# MUX_circuits.net
KiCad netlist of a schematic drawn in EAGLE
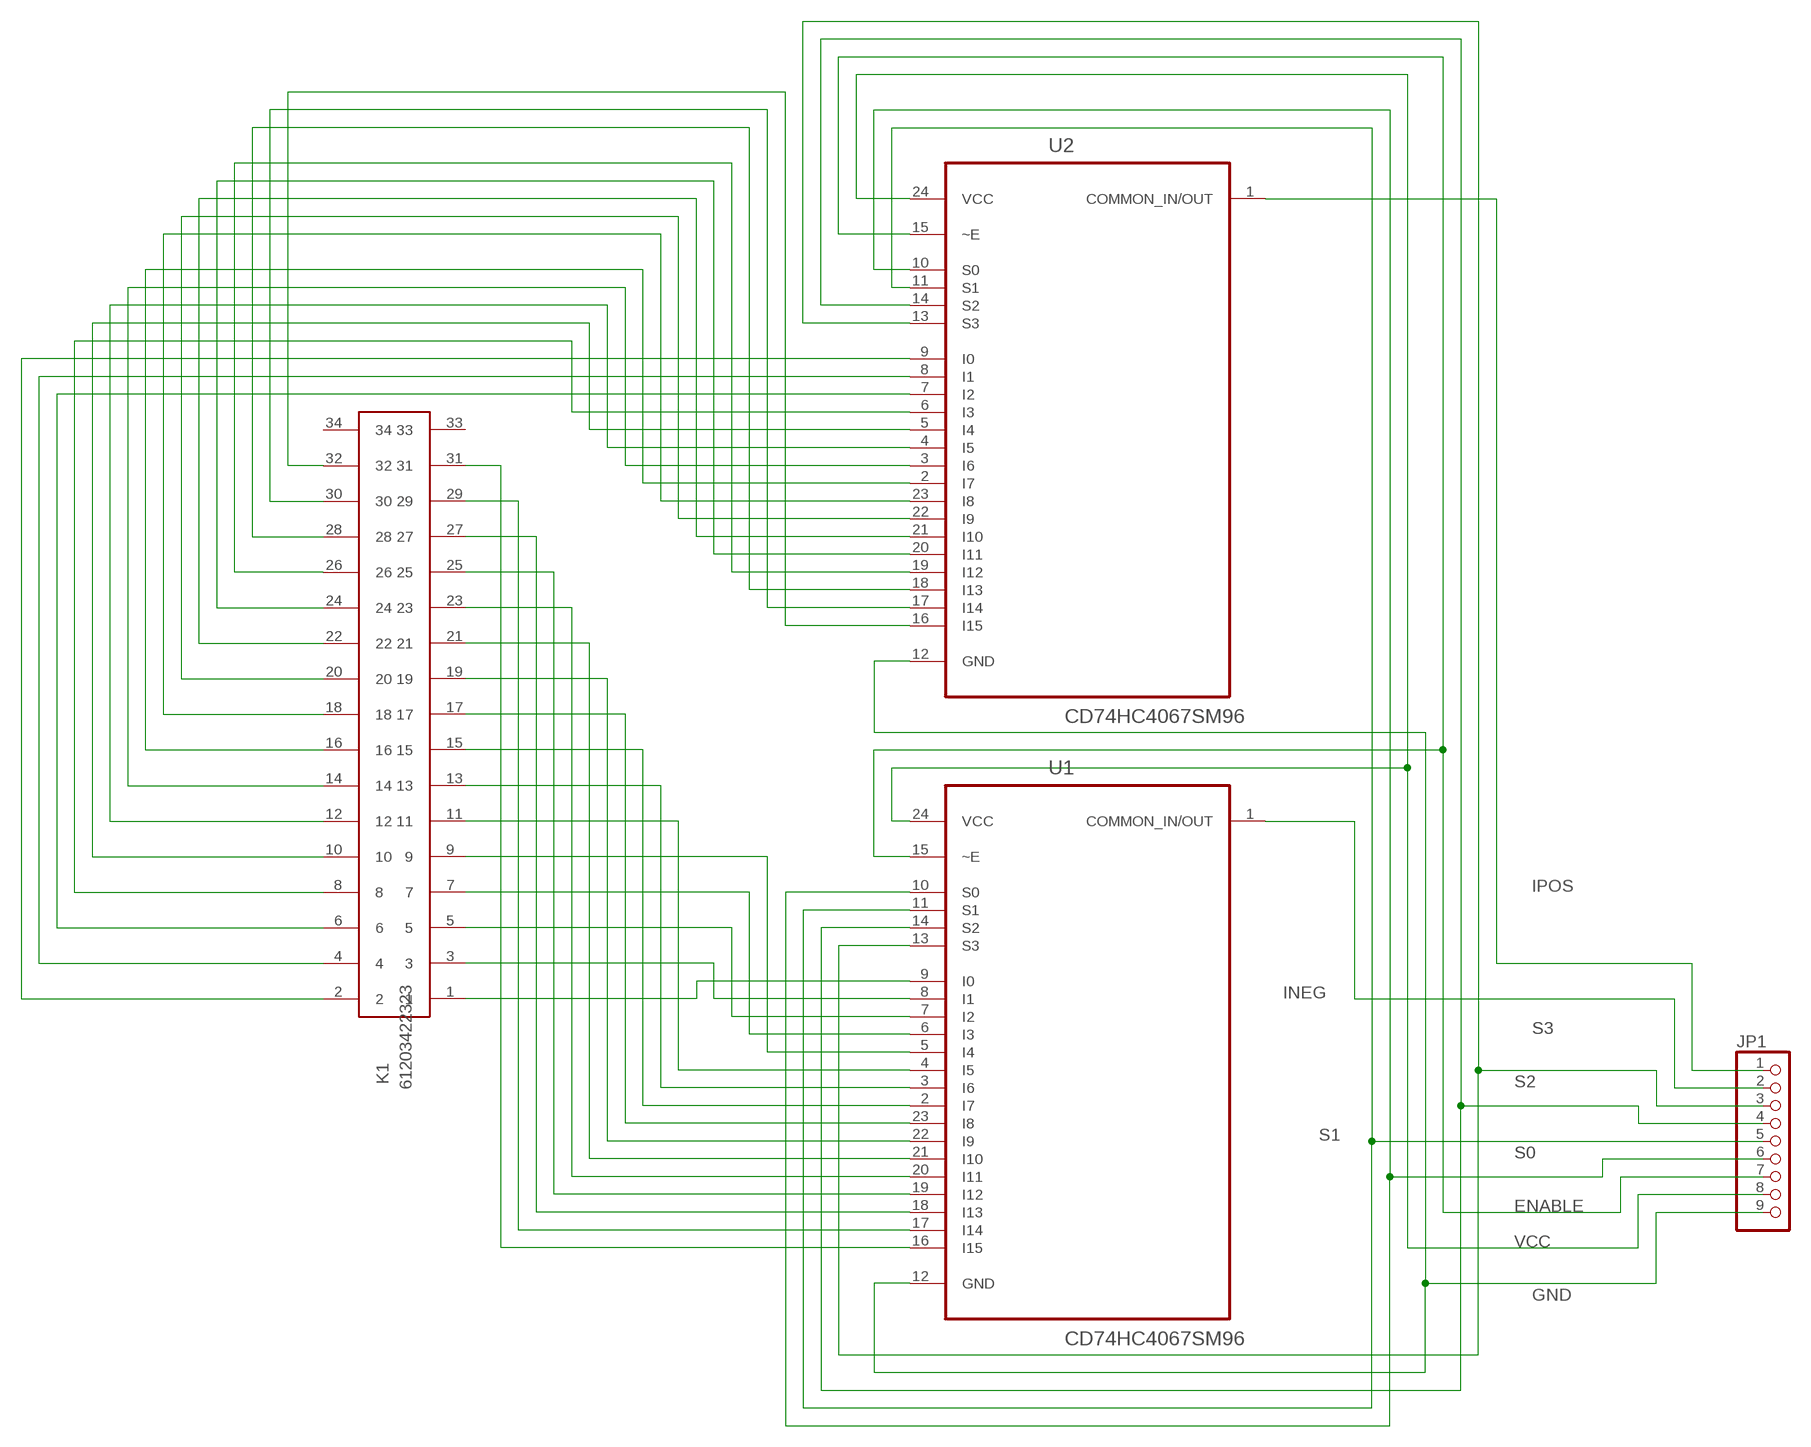
[diagram p0: schematic, sheet 1]

(export (version "E")
  (design (tool "Eeschema 10.0.6"))
  (components
    (comp (ref "JP1")
      (value "PINHD-1X9")
      (footprint "eagle-import:1X09")
      (libsource (lib "eagle-import") (part "PINHD-1X9"))
    )
    (comp (ref "K1")
      (value "61203422323")
      (footprint "eagle-import:61203422323")
      (libsource (lib "eagle-import") (part "61203422323"))
    )
    (comp (ref "U1")
      (value "CD74HC4067SM96")
      (footprint "eagle-import:SOP65P780X200-24N")
      (libsource (lib "eagle-import") (part "CD74HC4067SM96"))
    )
    (comp (ref "U2")
      (value "CD74HC4067SM96")
      (footprint "eagle-import:SOP65P780X200-24N")
      (libsource (lib "eagle-import") (part "CD74HC4067SM96"))
    )
  )
  (nets
    (net (code "1") (name "/ENABLE") (class "Default")
      (node (ref "JP1") (pin "7") (pinfunction "7_7") (pintype "passive"))
      (node (ref "U1") (pin "15") (pinfunction "~{E}_15") (pintype "input"))
      (node (ref "U2") (pin "15") (pinfunction "~{E}_15") (pintype "input"))
    )
    (net (code "2") (name "/GND") (class "Default")
      (node (ref "JP1") (pin "9") (pinfunction "9_9") (pintype "passive"))
      (node (ref "U1") (pin "12") (pinfunction "GND_12") (pintype "passive"))
      (node (ref "U2") (pin "12") (pinfunction "GND_12") (pintype "passive"))
    )
    (net (code "3") (name "/INEG") (class "Default")
      (node (ref "JP1") (pin "2") (pinfunction "2_2") (pintype "passive"))
      (node (ref "U1") (pin "1") (pinfunction "COMMON_IN/OUT_1") (pintype "bidirectional"))
    )
    (net (code "4") (name "/IPOS") (class "Default")
      (node (ref "JP1") (pin "1") (pinfunction "1_1") (pintype "passive"))
      (node (ref "U2") (pin "1") (pinfunction "COMMON_IN/OUT_1") (pintype "bidirectional"))
    )
    (net (code "5") (name "/S0") (class "Default")
      (node (ref "JP1") (pin "6") (pinfunction "6_6") (pintype "passive"))
      (node (ref "U1") (pin "10") (pinfunction "S0_10") (pintype "input"))
      (node (ref "U2") (pin "10") (pinfunction "S0_10") (pintype "input"))
    )
    (net (code "6") (name "/S1") (class "Default")
      (node (ref "JP1") (pin "5") (pinfunction "5_5") (pintype "passive"))
      (node (ref "U1") (pin "11") (pinfunction "S1_11") (pintype "input"))
      (node (ref "U2") (pin "11") (pinfunction "S1_11") (pintype "input"))
    )
    (net (code "7") (name "/S2") (class "Default")
      (node (ref "JP1") (pin "4") (pinfunction "4_4") (pintype "passive"))
      (node (ref "U1") (pin "14") (pinfunction "S2_14") (pintype "input"))
      (node (ref "U2") (pin "14") (pinfunction "S2_14") (pintype "input"))
    )
    (net (code "8") (name "/S3") (class "Default")
      (node (ref "JP1") (pin "3") (pinfunction "3_3") (pintype "passive"))
      (node (ref "U1") (pin "13") (pinfunction "S3_13") (pintype "input"))
      (node (ref "U2") (pin "13") (pinfunction "S3_13") (pintype "input"))
    )
    (net (code "9") (name "/VCC") (class "Default")
      (node (ref "JP1") (pin "8") (pinfunction "8_8") (pintype "passive"))
      (node (ref "U1") (pin "24") (pinfunction "VCC_24") (pintype "power_in"))
      (node (ref "U2") (pin "24") (pinfunction "VCC_24") (pintype "power_in"))
    )
    (net (code "10") (name "Net-(U1-I0)") (class "Default")
      (node (ref "K1") (pin "1") (pinfunction "1_1") (pintype "passive"))
      (node (ref "U1") (pin "9") (pinfunction "I0_9") (pintype "input"))
    )
    (net (code "11") (name "Net-(U1-I1)") (class "Default")
      (node (ref "K1") (pin "3") (pinfunction "3_3") (pintype "passive"))
      (node (ref "U1") (pin "8") (pinfunction "I1_8") (pintype "input"))
    )
    (net (code "12") (name "Net-(U1-I2)") (class "Default")
      (node (ref "K1") (pin "5") (pinfunction "5_5") (pintype "passive"))
      (node (ref "U1") (pin "7") (pinfunction "I2_7") (pintype "input"))
    )
    (net (code "13") (name "Net-(U1-I3)") (class "Default")
      (node (ref "K1") (pin "7") (pinfunction "7_7") (pintype "passive"))
      (node (ref "U1") (pin "6") (pinfunction "I3_6") (pintype "input"))
    )
    (net (code "14") (name "Net-(U1-I4)") (class "Default")
      (node (ref "K1") (pin "9") (pinfunction "9_9") (pintype "passive"))
      (node (ref "U1") (pin "5") (pinfunction "I4_5") (pintype "input"))
    )
    (net (code "15") (name "Net-(U1-I5)") (class "Default")
      (node (ref "K1") (pin "11") (pinfunction "11_11") (pintype "passive"))
      (node (ref "U1") (pin "4") (pinfunction "I5_4") (pintype "input"))
    )
    (net (code "16") (name "Net-(U1-I6)") (class "Default")
      (node (ref "K1") (pin "13") (pinfunction "13_13") (pintype "passive"))
      (node (ref "U1") (pin "3") (pinfunction "I6_3") (pintype "input"))
    )
    (net (code "17") (name "Net-(U1-I7)") (class "Default")
      (node (ref "K1") (pin "15") (pinfunction "15_15") (pintype "passive"))
      (node (ref "U1") (pin "2") (pinfunction "I7_2") (pintype "input"))
    )
    (net (code "18") (name "Net-(U1-I8)") (class "Default")
      (node (ref "K1") (pin "17") (pinfunction "17_17") (pintype "passive"))
      (node (ref "U1") (pin "23") (pinfunction "I8_23") (pintype "input"))
    )
    (net (code "19") (name "Net-(U1-I9)") (class "Default")
      (node (ref "K1") (pin "19") (pinfunction "19_19") (pintype "passive"))
      (node (ref "U1") (pin "22") (pinfunction "I9_22") (pintype "input"))
    )
    (net (code "20") (name "Net-(U1-I10)") (class "Default")
      (node (ref "K1") (pin "21") (pinfunction "21_21") (pintype "passive"))
      (node (ref "U1") (pin "21") (pinfunction "I10_21") (pintype "input"))
    )
    (net (code "21") (name "Net-(U1-I11)") (class "Default")
      (node (ref "K1") (pin "23") (pinfunction "23_23") (pintype "passive"))
      (node (ref "U1") (pin "20") (pinfunction "I11_20") (pintype "input"))
    )
    (net (code "22") (name "Net-(U1-I12)") (class "Default")
      (node (ref "K1") (pin "25") (pinfunction "25_25") (pintype "passive"))
      (node (ref "U1") (pin "19") (pinfunction "I12_19") (pintype "input"))
    )
    (net (code "23") (name "Net-(U1-I13)") (class "Default")
      (node (ref "K1") (pin "27") (pinfunction "27_27") (pintype "passive"))
      (node (ref "U1") (pin "18") (pinfunction "I13_18") (pintype "input"))
    )
    (net (code "24") (name "Net-(U1-I14)") (class "Default")
      (node (ref "K1") (pin "29") (pinfunction "29_29") (pintype "passive"))
      (node (ref "U1") (pin "17") (pinfunction "I14_17") (pintype "input"))
    )
    (net (code "25") (name "Net-(U1-I15)") (class "Default")
      (node (ref "K1") (pin "31") (pinfunction "31_31") (pintype "passive"))
      (node (ref "U1") (pin "16") (pinfunction "I15_16") (pintype "input"))
    )
    (net (code "26") (name "Net-(U2-I0)") (class "Default")
      (node (ref "K1") (pin "2") (pinfunction "2_2") (pintype "passive"))
      (node (ref "U2") (pin "9") (pinfunction "I0_9") (pintype "input"))
    )
    (net (code "27") (name "Net-(U2-I1)") (class "Default")
      (node (ref "K1") (pin "4") (pinfunction "4_4") (pintype "passive"))
      (node (ref "U2") (pin "8") (pinfunction "I1_8") (pintype "input"))
    )
    (net (code "28") (name "Net-(U2-I2)") (class "Default")
      (node (ref "K1") (pin "6") (pinfunction "6_6") (pintype "passive"))
      (node (ref "U2") (pin "7") (pinfunction "I2_7") (pintype "input"))
    )
    (net (code "29") (name "Net-(U2-I3)") (class "Default")
      (node (ref "K1") (pin "8") (pinfunction "8_8") (pintype "passive"))
      (node (ref "U2") (pin "6") (pinfunction "I3_6") (pintype "input"))
    )
    (net (code "30") (name "Net-(U2-I4)") (class "Default")
      (node (ref "K1") (pin "10") (pinfunction "10_10") (pintype "passive"))
      (node (ref "U2") (pin "5") (pinfunction "I4_5") (pintype "input"))
    )
    (net (code "31") (name "Net-(U2-I5)") (class "Default")
      (node (ref "K1") (pin "12") (pinfunction "12_12") (pintype "passive"))
      (node (ref "U2") (pin "4") (pinfunction "I5_4") (pintype "input"))
    )
    (net (code "32") (name "Net-(U2-I6)") (class "Default")
      (node (ref "K1") (pin "14") (pinfunction "14_14") (pintype "passive"))
      (node (ref "U2") (pin "3") (pinfunction "I6_3") (pintype "input"))
    )
    (net (code "33") (name "Net-(U2-I7)") (class "Default")
      (node (ref "K1") (pin "16") (pinfunction "16_16") (pintype "passive"))
      (node (ref "U2") (pin "2") (pinfunction "I7_2") (pintype "input"))
    )
    (net (code "34") (name "Net-(U2-I8)") (class "Default")
      (node (ref "K1") (pin "18") (pinfunction "18_18") (pintype "passive"))
      (node (ref "U2") (pin "23") (pinfunction "I8_23") (pintype "input"))
    )
    (net (code "35") (name "Net-(U2-I9)") (class "Default")
      (node (ref "K1") (pin "20") (pinfunction "20_20") (pintype "passive"))
      (node (ref "U2") (pin "22") (pinfunction "I9_22") (pintype "input"))
    )
    (net (code "36") (name "Net-(U2-I10)") (class "Default")
      (node (ref "K1") (pin "22") (pinfunction "22_22") (pintype "passive"))
      (node (ref "U2") (pin "21") (pinfunction "I10_21") (pintype "input"))
    )
    (net (code "37") (name "Net-(U2-I11)") (class "Default")
      (node (ref "K1") (pin "24") (pinfunction "24_24") (pintype "passive"))
      (node (ref "U2") (pin "20") (pinfunction "I11_20") (pintype "input"))
    )
    (net (code "38") (name "Net-(U2-I12)") (class "Default")
      (node (ref "K1") (pin "26") (pinfunction "26_26") (pintype "passive"))
      (node (ref "U2") (pin "19") (pinfunction "I12_19") (pintype "input"))
    )
    (net (code "39") (name "Net-(U2-I13)") (class "Default")
      (node (ref "K1") (pin "28") (pinfunction "28_28") (pintype "passive"))
      (node (ref "U2") (pin "18") (pinfunction "I13_18") (pintype "input"))
    )
    (net (code "40") (name "Net-(U2-I14)") (class "Default")
      (node (ref "K1") (pin "30") (pinfunction "30_30") (pintype "passive"))
      (node (ref "U2") (pin "17") (pinfunction "I14_17") (pintype "input"))
    )
    (net (code "41") (name "Net-(U2-I15)") (class "Default")
      (node (ref "K1") (pin "32") (pinfunction "32_32") (pintype "passive"))
      (node (ref "U2") (pin "16") (pinfunction "I15_16") (pintype "input"))
    )
    (net (code "42") (name "unconnected-(K1-Pad33)") (class "Default")
      (node (ref "K1") (pin "33") (pinfunction "33_33") (pintype "passive"))
    )
    (net (code "43") (name "unconnected-(K1-Pad34)") (class "Default")
      (node (ref "K1") (pin "34") (pinfunction "34_34") (pintype "passive"))
    )
  )
)
